# Schematic_1.net
KiCad netlist of a schematic drawn in EAGLE
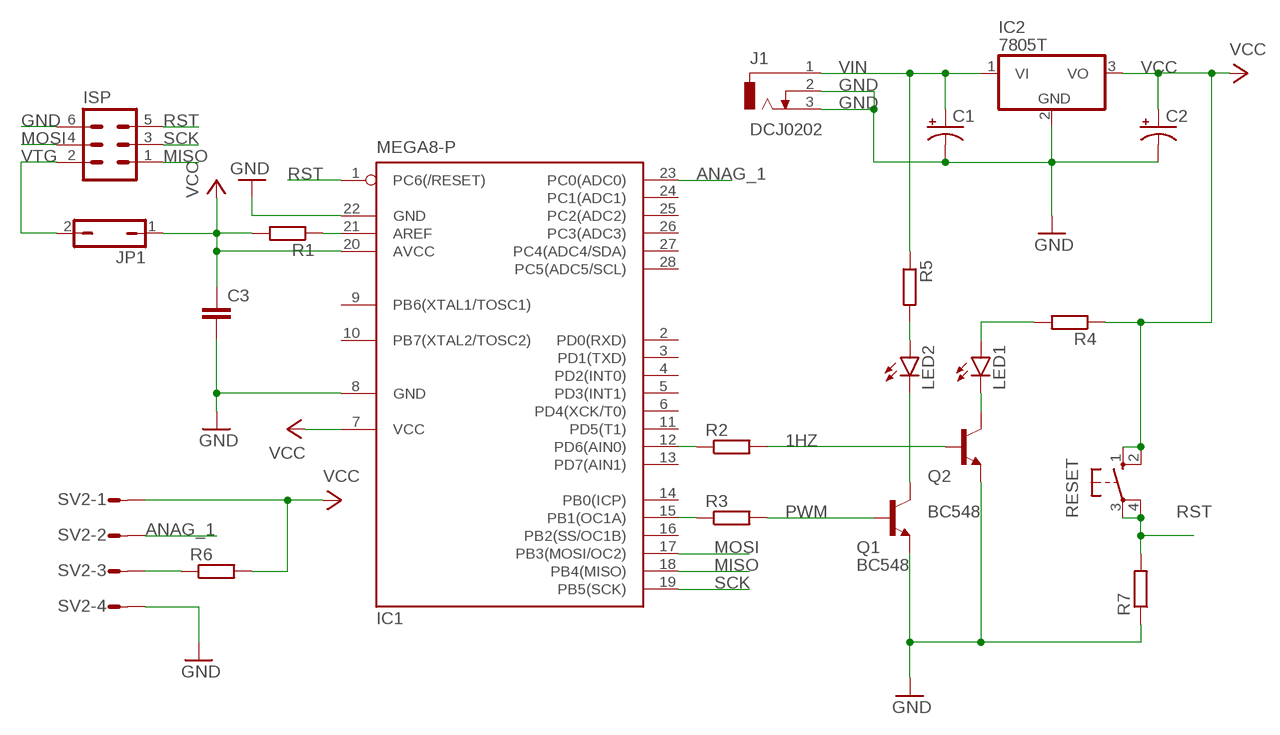
[diagram p0: schematic, sheet 1]

(export (version "E")
  (design (tool "Eeschema 10.0.6"))
  (components
    (comp (ref "C1")
      (value "CPOL-USE2.5-7")
      (footprint "eagle-import:E2,5-7")
      (libsource (lib "eagle-import") (part "CPOL-USE2.5-7"))
    )
    (comp (ref "C2")
      (value "CPOL-USE2.5-7")
      (footprint "eagle-import:E2,5-7")
      (libsource (lib "eagle-import") (part "CPOL-USE2.5-7"))
    )
    (comp (ref "C3")
      (value "C-EU025-025X050")
      (footprint "eagle-import:C025-025X050")
      (libsource (lib "eagle-import") (part "C-EU025-025X050"))
    )
    (comp (ref "IC1")
      (value "MEGA8-P")
      (footprint "eagle-import:DIL28-3")
      (libsource (lib "eagle-import") (part "MEGA8-P"))
    )
    (comp (ref "IC2")
      (value "7805T")
      (footprint "eagle-import:TO220H")
      (libsource (lib "eagle-import") (part "78T05"))
    )
    (comp (ref "ISP")
      (value "ML6")
      (footprint "eagle-import:ML6")
      (libsource (lib "eagle-import") (part "ML6"))
    )
    (comp (ref "J1")
      (value "DCJ0202")
      (footprint "eagle-import:DCJ0202")
      (libsource (lib "eagle-import") (part "DCJ0202"))
    )
    (comp (ref "JP1")
      (value "JP1Q")
      (footprint "eagle-import:JP1")
      (libsource (lib "eagle-import") (part "JP1Q"))
    )
    (comp (ref "LED1")
      (value "LEDB156")
      (footprint "eagle-import:Q62902-B156")
      (libsource (lib "eagle-import") (part "LEDB156"))
    )
    (comp (ref "LED2")
      (value "LEDB156")
      (footprint "eagle-import:Q62902-B156")
      (libsource (lib "eagle-import") (part "LEDB156"))
    )
    (comp (ref "Q1")
      (value "BC548")
      (footprint "eagle-import:TO92-EBC")
      (libsource (lib "eagle-import") (part "BC548"))
    )
    (comp (ref "Q2")
      (value "BC548")
      (footprint "eagle-import:TO92-EBC")
      (libsource (lib "eagle-import") (part "BC548"))
    )
    (comp (ref "R1")
      (value "R-EU_0207/7")
      (footprint "eagle-import:0207_7")
      (libsource (lib "eagle-import") (part "R-EU_0207/7"))
    )
    (comp (ref "R2")
      (value "R-EU_0207/7")
      (footprint "eagle-import:0207_7")
      (libsource (lib "eagle-import") (part "R-EU_0207/7"))
    )
    (comp (ref "R3")
      (value "R-EU_0207/7")
      (footprint "eagle-import:0207_7")
      (libsource (lib "eagle-import") (part "R-EU_0207/7"))
    )
    (comp (ref "R4")
      (value "R-EU_0207/7")
      (footprint "eagle-import:0207_7")
      (libsource (lib "eagle-import") (part "R-EU_0207/7"))
    )
    (comp (ref "R5")
      (value "R-EU_0207/7")
      (footprint "eagle-import:0207_7")
      (libsource (lib "eagle-import") (part "R-EU_0207/7"))
    )
    (comp (ref "R6")
      (value "R-EU_0207/7")
      (footprint "eagle-import:0207_7")
      (libsource (lib "eagle-import") (part "R-EU_0207/7"))
    )
    (comp (ref "R7")
      (value "R-EU_0207/7")
      (footprint "eagle-import:0207_7")
      (libsource (lib "eagle-import") (part "R-EU_0207/7"))
    )
    (comp (ref "RESET")
      (value "10-XX")
      (footprint "eagle-import:B3F-10XX")
      (fields (field (name "MPN") "B3F-1000"))
      (libsource (lib "eagle-import") (part "10-XX"))
    )
    (comp (ref "SV2")
      (value "L04P")
      (footprint "eagle-import:L04P")
      (libsource (lib "eagle-import") (part "L04P"))
    )
  )
  (nets
    (net (code "1") (name "/1HZ") (class "Default")
      (node (ref "Q2") (pin "B") (pinfunction "B_B") (pintype "passive"))
      (node (ref "R2") (pin "2") (pinfunction "2_2") (pintype "passive"))
    )
    (net (code "2") (name "/ANAG_1") (class "Default")
      (node (ref "IC1") (pin "23") (pinfunction "PC0(ADC0)_23") (pintype "bidirectional"))
      (node (ref "SV2") (pin "2") (pinfunction "S_2") (pintype "passive"))
    )
    (net (code "3") (name "/MISO") (class "Default")
      (node (ref "IC1") (pin "18") (pinfunction "PB4(MISO)_18") (pintype "bidirectional"))
      (node (ref "ISP") (pin "1") (pinfunction "1_1") (pintype "passive"))
    )
    (net (code "4") (name "/MOSI") (class "Default")
      (node (ref "IC1") (pin "17") (pinfunction "PB3(MOSI/OC2)_17") (pintype "bidirectional"))
      (node (ref "ISP") (pin "4") (pinfunction "4_4") (pintype "passive"))
    )
    (net (code "5") (name "/PWM") (class "Default")
      (node (ref "Q1") (pin "B") (pinfunction "B_B") (pintype "passive"))
      (node (ref "R3") (pin "2") (pinfunction "2_2") (pintype "passive"))
    )
    (net (code "6") (name "/RST") (class "Default")
      (node (ref "IC1") (pin "1") (pinfunction "PC6(/RESET)_1") (pintype "bidirectional"))
      (node (ref "ISP") (pin "5") (pinfunction "5_5") (pintype "passive"))
      (node (ref "R7") (pin "2") (pinfunction "2_2") (pintype "passive"))
      (node (ref "RESET") (pin "3") (pinfunction "P_3") (pintype "passive"))
      (node (ref "RESET") (pin "4") (pinfunction "P1_4") (pintype "passive"))
    )
    (net (code "7") (name "/SCK") (class "Default")
      (node (ref "IC1") (pin "19") (pinfunction "PB5(SCK)_19") (pintype "bidirectional"))
      (node (ref "ISP") (pin "3") (pinfunction "3_3") (pintype "passive"))
    )
    (net (code "8") (name "/VIN") (class "Default")
      (node (ref "C1") (pin "+") (pinfunction "+_+") (pintype "passive"))
      (node (ref "IC2") (pin "1") (pinfunction "VI_1") (pintype "input"))
      (node (ref "J1") (pin "1") (pinfunction "1_1") (pintype "passive"))
      (node (ref "R5") (pin "1") (pinfunction "1_1") (pintype "passive"))
    )
    (net (code "9") (name "/VTG") (class "Default")
      (node (ref "ISP") (pin "2") (pinfunction "2_2") (pintype "passive"))
      (node (ref "JP1") (pin "2") (pinfunction "2_2") (pintype "passive"))
    )
    (net (code "10") (name "GND") (class "Default")
      (node (ref "C1") (pin "-") (pinfunction "-_-") (pintype "passive"))
      (node (ref "C2") (pin "-") (pinfunction "-_-") (pintype "passive"))
      (node (ref "C3") (pin "2") (pinfunction "2_2") (pintype "passive"))
      (node (ref "IC1") (pin "22") (pinfunction "GND_22") (pintype "power_in"))
      (node (ref "IC1") (pin "8") (pinfunction "GND_8") (pintype "power_in"))
      (node (ref "IC2") (pin "2") (pinfunction "GND_2") (pintype "passive"))
      (node (ref "ISP") (pin "6") (pinfunction "6_6") (pintype "passive"))
      (node (ref "J1") (pin "2") (pinfunction "2_2") (pintype "passive"))
      (node (ref "J1") (pin "3") (pinfunction "3_3") (pintype "passive"))
      (node (ref "Q1") (pin "E") (pinfunction "E_E") (pintype "passive"))
      (node (ref "Q2") (pin "E") (pinfunction "E_E") (pintype "passive"))
      (node (ref "R7") (pin "1") (pinfunction "1_1") (pintype "passive"))
      (node (ref "SV2") (pin "4") (pinfunction "S_4") (pintype "passive"))
    )
    (net (code "11") (name "Net-(IC1-AREF)") (class "Default")
      (node (ref "IC1") (pin "21") (pinfunction "AREF_21") (pintype "passive"))
      (node (ref "R1") (pin "1") (pinfunction "1_1") (pintype "passive"))
    )
    (net (code "12") (name "Net-(IC1-PB1(OC1A))") (class "Default")
      (node (ref "IC1") (pin "15") (pinfunction "PB1(OC1A)_15") (pintype "bidirectional"))
      (node (ref "R3") (pin "1") (pinfunction "1_1") (pintype "passive"))
    )
    (net (code "13") (name "Net-(IC1-PD6(AIN0))") (class "Default")
      (node (ref "IC1") (pin "12") (pinfunction "PD6(AIN0)_12") (pintype "bidirectional"))
      (node (ref "R2") (pin "1") (pinfunction "1_1") (pintype "passive"))
    )
    (net (code "14") (name "Net-(LED1-C)") (class "Default")
      (node (ref "LED1") (pin "K") (pinfunction "C_K") (pintype "passive"))
      (node (ref "Q2") (pin "C") (pinfunction "C_C") (pintype "passive"))
    )
    (net (code "15") (name "Net-(LED1-PadA)") (class "Default")
      (node (ref "LED1") (pin "A") (pinfunction "A_A") (pintype "passive"))
      (node (ref "R4") (pin "2") (pinfunction "2_2") (pintype "passive"))
    )
    (net (code "16") (name "Net-(LED2-C)") (class "Default")
      (node (ref "LED2") (pin "K") (pinfunction "C_K") (pintype "passive"))
      (node (ref "Q1") (pin "C") (pinfunction "C_C") (pintype "passive"))
    )
    (net (code "17") (name "Net-(LED2-PadA)") (class "Default")
      (node (ref "LED2") (pin "A") (pinfunction "A_A") (pintype "passive"))
      (node (ref "R5") (pin "2") (pinfunction "2_2") (pintype "passive"))
    )
    (net (code "18") (name "Net-(SV2C-S)") (class "Default")
      (node (ref "R6") (pin "1") (pinfunction "1_1") (pintype "passive"))
      (node (ref "SV2") (pin "3") (pinfunction "S_3") (pintype "passive"))
    )
    (net (code "19") (name "VCC") (class "Default")
      (node (ref "C2") (pin "+") (pinfunction "+_+") (pintype "passive"))
      (node (ref "C3") (pin "1") (pinfunction "1_1") (pintype "passive"))
      (node (ref "IC1") (pin "20") (pinfunction "AVCC_20") (pintype "power_in"))
      (node (ref "IC1") (pin "7") (pinfunction "VCC_7") (pintype "power_in"))
      (node (ref "IC2") (pin "3") (pinfunction "VO_3") (pintype "passive"))
      (node (ref "JP1") (pin "1") (pinfunction "1_1") (pintype "passive"))
      (node (ref "R1") (pin "2") (pinfunction "2_2") (pintype "passive"))
      (node (ref "R4") (pin "1") (pinfunction "1_1") (pintype "passive"))
      (node (ref "R6") (pin "2") (pinfunction "2_2") (pintype "passive"))
      (node (ref "RESET") (pin "1") (pinfunction "S_1") (pintype "passive"))
      (node (ref "RESET") (pin "2") (pinfunction "S1_2") (pintype "passive"))
      (node (ref "SV2") (pin "1") (pinfunction "S_1") (pintype "passive"))
    )
    (net (code "20") (name "unconnected-(IC1-PB0(ICP)-Pad14)") (class "Default")
      (node (ref "IC1") (pin "14") (pinfunction "PB0(ICP)_14") (pintype "bidirectional"))
    )
    (net (code "21") (name "unconnected-(IC1-PB2(SS{slash}OC1B)-Pad16)") (class "Default")
      (node (ref "IC1") (pin "16") (pinfunction "PB2(SS/OC1B)_16") (pintype "bidirectional"))
    )
    (net (code "22") (name "unconnected-(IC1-PB6(XTAL1{slash}TOSC1)-Pad9)") (class "Default")
      (node (ref "IC1") (pin "9") (pinfunction "PB6(XTAL1/TOSC1)_9") (pintype "bidirectional"))
    )
    (net (code "23") (name "unconnected-(IC1-PB7(XTAL2{slash}TOSC2)-Pad10)") (class "Default")
      (node (ref "IC1") (pin "10") (pinfunction "PB7(XTAL2/TOSC2)_10") (pintype "bidirectional"))
    )
    (net (code "24") (name "unconnected-(IC1-PC1(ADC1)-Pad24)") (class "Default")
      (node (ref "IC1") (pin "24") (pinfunction "PC1(ADC1)_24") (pintype "bidirectional"))
    )
    (net (code "25") (name "unconnected-(IC1-PC2(ADC2)-Pad25)") (class "Default")
      (node (ref "IC1") (pin "25") (pinfunction "PC2(ADC2)_25") (pintype "bidirectional"))
    )
    (net (code "26") (name "unconnected-(IC1-PC3(ADC3)-Pad26)") (class "Default")
      (node (ref "IC1") (pin "26") (pinfunction "PC3(ADC3)_26") (pintype "bidirectional"))
    )
    (net (code "27") (name "unconnected-(IC1-PC4(ADC4{slash}SDA)-Pad27)") (class "Default")
      (node (ref "IC1") (pin "27") (pinfunction "PC4(ADC4/SDA)_27") (pintype "bidirectional"))
    )
    (net (code "28") (name "unconnected-(IC1-PC5(ADC5{slash}SCL)-Pad28)") (class "Default")
      (node (ref "IC1") (pin "28") (pinfunction "PC5(ADC5/SCL)_28") (pintype "bidirectional"))
    )
    (net (code "29") (name "unconnected-(IC1-PD0(RXD)-Pad2)") (class "Default")
      (node (ref "IC1") (pin "2") (pinfunction "PD0(RXD)_2") (pintype "bidirectional"))
    )
    (net (code "30") (name "unconnected-(IC1-PD1(TXD)-Pad3)") (class "Default")
      (node (ref "IC1") (pin "3") (pinfunction "PD1(TXD)_3") (pintype "bidirectional"))
    )
    (net (code "31") (name "unconnected-(IC1-PD2(INT0)-Pad4)") (class "Default")
      (node (ref "IC1") (pin "4") (pinfunction "PD2(INT0)_4") (pintype "bidirectional"))
    )
    (net (code "32") (name "unconnected-(IC1-PD3(INT1)-Pad5)") (class "Default")
      (node (ref "IC1") (pin "5") (pinfunction "PD3(INT1)_5") (pintype "bidirectional"))
    )
    (net (code "33") (name "unconnected-(IC1-PD4(XCK{slash}T0)-Pad6)") (class "Default")
      (node (ref "IC1") (pin "6") (pinfunction "PD4(XCK/T0)_6") (pintype "bidirectional"))
    )
    (net (code "34") (name "unconnected-(IC1-PD5(T1)-Pad11)") (class "Default")
      (node (ref "IC1") (pin "11") (pinfunction "PD5(T1)_11") (pintype "bidirectional"))
    )
    (net (code "35") (name "unconnected-(IC1-PD7(AIN1)-Pad13)") (class "Default")
      (node (ref "IC1") (pin "13") (pinfunction "PD7(AIN1)_13") (pintype "bidirectional"))
    )
  )
)
